# EVENTCTRL_ACQ.net
KiCad netlist of a schematic drawn in Altium Designer
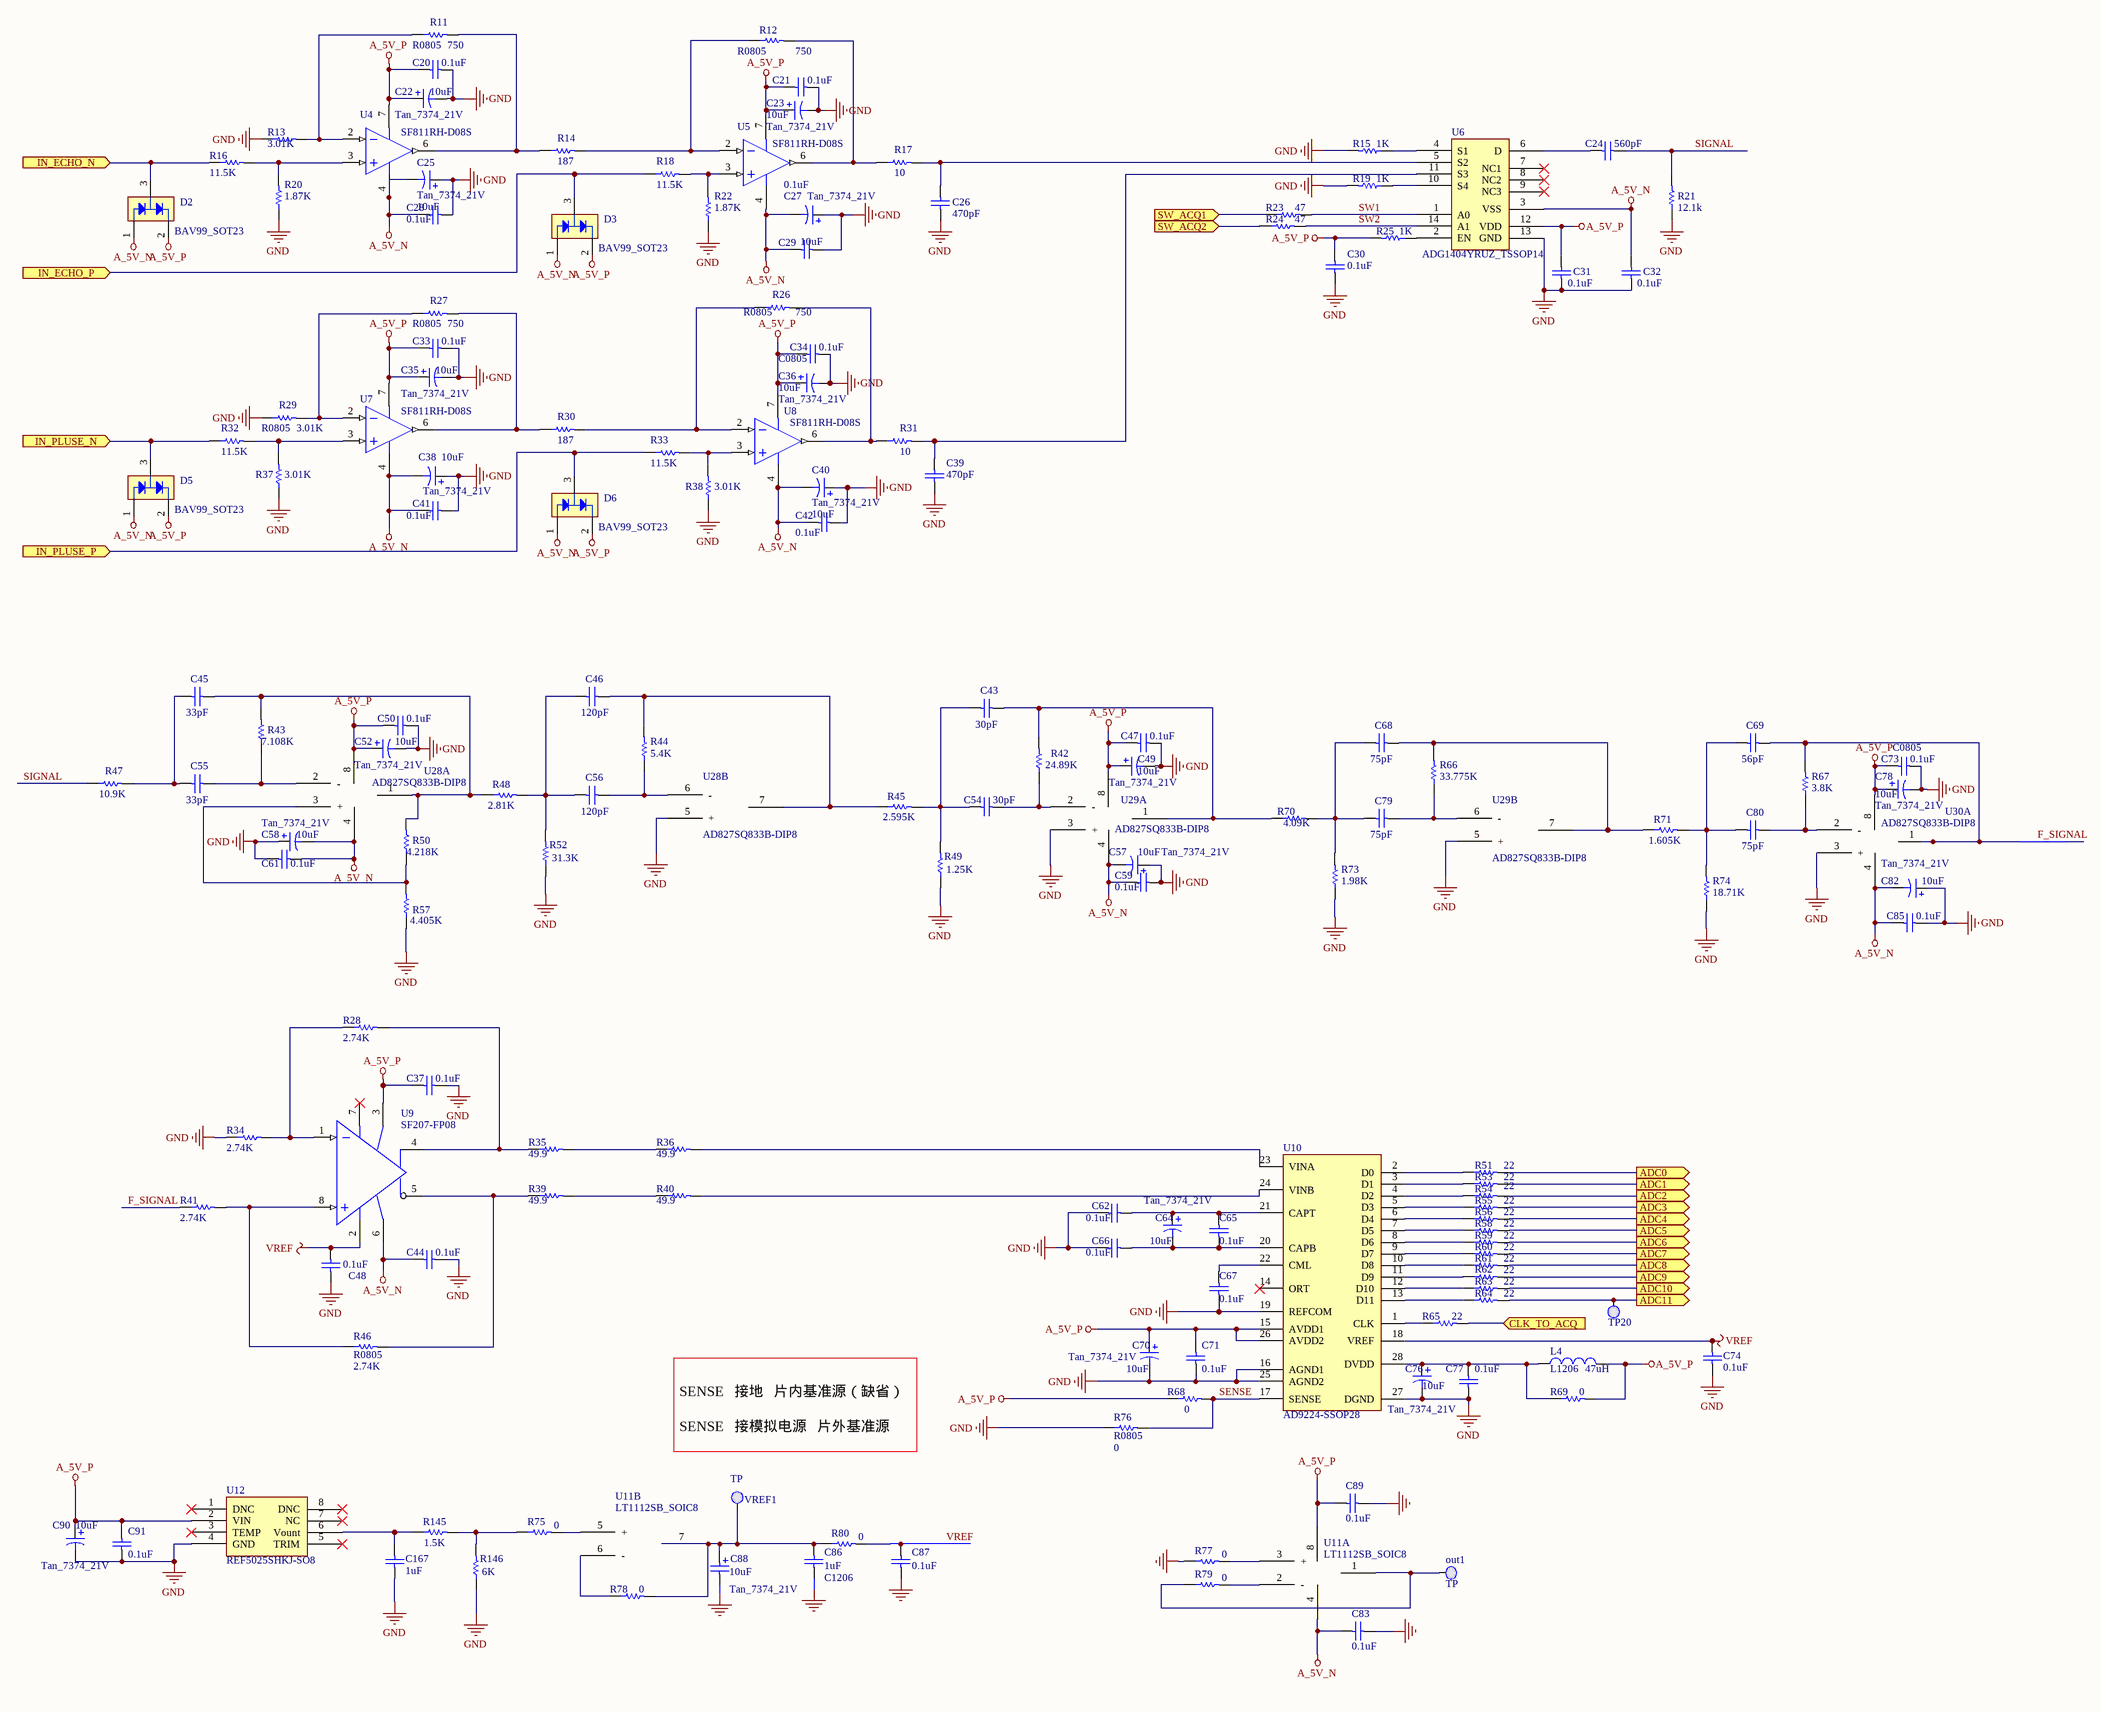
[diagram p0: EVENTCTRL_ACQ.SchDoc]

(export (version "E")
  (design (tool "Eeschema 10.0.6"))
  (components
    (comp (ref "C20")
      (value "0.1uF")
      (footprint "0805")
      (description "Capacitor")
      (fields (field (name "Comment") "C0805"))
      (libsource (lib "Miscellaneous Devices") (part "Cap"))
    )
    (comp (ref "C21")
      (value "0.1uF")
      (footprint "0805")
      (description "Capacitor")
      (fields (field (name "Comment") "C0805"))
      (libsource (lib "Miscellaneous Devices") (part "Cap"))
    )
    (comp (ref "C22")
      (value "Tan_7374_21V")
      (footprint "7343")
      (description "Polarized Capacitor (Surface Mount)")
      (fields (field (name "ALTIUM_VALUE") "10uF") (field (name "PUBLISHER") "Altium Limited"))
      (libsource (lib "Miscellaneous Devices") (part "Cap Pol3"))
    )
    (comp (ref "C23")
      (value "Tan_7374_21V")
      (footprint "7343")
      (description "Polarized Capacitor (Surface Mount)")
      (fields (field (name "ALTIUM_VALUE") "10uF") (field (name "PUBLISHER") "Altium Limited"))
      (libsource (lib "Miscellaneous Devices") (part "Cap Pol3"))
    )
    (comp (ref "C24")
      (value "560pF")
      (footprint "0805")
      (description "Capacitor")
      (fields (field (name "Comment") "C0805"))
      (libsource (lib "Miscellaneous Devices") (part "Cap"))
    )
    (comp (ref "C25")
      (value "Tan_7374_21V")
      (footprint "7343")
      (description "Polarized Capacitor (Surface Mount)")
      (fields (field (name "ALTIUM_VALUE") "10uF") (field (name "PUBLISHER") "Altium Limited"))
      (libsource (lib "Miscellaneous Devices") (part "Cap Pol3"))
    )
    (comp (ref "C26")
      (value "470pF")
      (footprint "0805")
      (description "Capacitor")
      (fields (field (name "Comment") "C0805"))
      (libsource (lib "Miscellaneous Devices") (part "Cap"))
    )
    (comp (ref "C27")
      (value "Tan_7374_21V")
      (footprint "7343")
      (description "Polarized Capacitor (Surface Mount)")
      (fields (field (name "ALTIUM_VALUE") "10uF") (field (name "PUBLISHER") "Altium Limited"))
      (libsource (lib "Miscellaneous Devices") (part "Cap Pol3"))
    )
    (comp (ref "C28")
      (value "0.1uF")
      (footprint "0805")
      (description "Capacitor")
      (fields (field (name "Comment") "C0805"))
      (libsource (lib "Miscellaneous Devices") (part "Cap"))
    )
    (comp (ref "C29")
      (value "0.1uF")
      (footprint "0805")
      (description "Capacitor")
      (fields (field (name "Comment") "C0805"))
      (libsource (lib "Miscellaneous Devices") (part "Cap"))
    )
    (comp (ref "C30")
      (value "0.1uF")
      (footprint "0805")
      (description "Capacitor")
      (fields (field (name "Comment") "C0805"))
      (libsource (lib "Miscellaneous Devices") (part "Cap"))
    )
    (comp (ref "C31")
      (value "0.1uF")
      (footprint "0805")
      (description "Capacitor")
      (fields (field (name "Comment") "C0805"))
      (libsource (lib "Miscellaneous Devices") (part "Cap"))
    )
    (comp (ref "C32")
      (value "0.1uF")
      (footprint "0805")
      (description "Capacitor")
      (fields (field (name "Comment") "C0805"))
      (libsource (lib "Miscellaneous Devices") (part "Cap"))
    )
    (comp (ref "C33")
      (value "0.1uF")
      (footprint "0805")
      (description "Capacitor")
      (fields (field (name "Comment") "C0805"))
      (libsource (lib "Miscellaneous Devices") (part "Cap"))
    )
    (comp (ref "C34")
      (value "0.1uF")
      (footprint "0805")
      (description "Capacitor")
      (fields (field (name "PACKAGEREFERENCE") "C0805") (field (name "Comment") "C0805"))
      (libsource (lib "Miscellaneous Devices") (part "Cap"))
    )
    (comp (ref "C35")
      (value "Tan_7374_21V")
      (footprint "7343")
      (description "Polarized Capacitor (Surface Mount)")
      (fields (field (name "ALTIUM_VALUE") "10uF") (field (name "PUBLISHER") "Altium Limited"))
      (libsource (lib "Miscellaneous Devices") (part "Cap Pol3"))
    )
    (comp (ref "C36")
      (value "Tan_7374_21V")
      (footprint "7343")
      (description "Polarized Capacitor (Surface Mount)")
      (fields (field (name "ALTIUM_VALUE") "10uF") (field (name "PUBLISHER") "Altium Limited"))
      (libsource (lib "Miscellaneous Devices") (part "Cap Pol3"))
    )
    (comp (ref "C37")
      (value "0.1uF")
      (footprint "0805")
      (description "Capacitor")
      (fields (field (name "Comment") "C0805"))
      (libsource (lib "Miscellaneous Devices") (part "Cap"))
    )
    (comp (ref "C38")
      (value "Tan_7374_21V")
      (footprint "7343")
      (description "Polarized Capacitor (Surface Mount)")
      (fields (field (name "ALTIUM_VALUE") "10uF") (field (name "PUBLISHER") "Altium Limited"))
      (libsource (lib "Miscellaneous Devices") (part "Cap Pol3"))
    )
    (comp (ref "C39")
      (value "470pF")
      (footprint "0805")
      (description "Capacitor")
      (fields (field (name "Comment") "C0805"))
      (libsource (lib "Miscellaneous Devices") (part "Cap"))
    )
    (comp (ref "C40")
      (value "Tan_7374_21V")
      (footprint "7343")
      (description "Polarized Capacitor (Surface Mount)")
      (fields (field (name "ALTIUM_VALUE") "10uF") (field (name "PUBLISHER") "Altium Limited"))
      (libsource (lib "Miscellaneous Devices") (part "Cap Pol3"))
    )
    (comp (ref "C41")
      (value "0.1uF")
      (footprint "0805")
      (description "Capacitor")
      (fields (field (name "Comment") "C0805"))
      (libsource (lib "Miscellaneous Devices") (part "Cap"))
    )
    (comp (ref "C42")
      (value "0.1uF")
      (footprint "0805")
      (description "Capacitor")
      (fields (field (name "Comment") "C0805"))
      (libsource (lib "Miscellaneous Devices") (part "Cap"))
    )
    (comp (ref "C43")
      (value "30pF")
      (footprint "0805")
      (description "Capacitor")
      (fields (field (name "Comment") "C0805") (field (name "PUBLISHER") "Altium Limited"))
      (libsource (lib "Miscellaneous Devices") (part "Cap"))
    )
    (comp (ref "C44")
      (value "0.1uF")
      (footprint "0805")
      (description "Capacitor")
      (fields (field (name "Comment") "C0805"))
      (libsource (lib "Miscellaneous Devices") (part "Cap"))
    )
    (comp (ref "C45")
      (value "33pF")
      (footprint "0805")
      (description "Capacitor")
      (fields (field (name "Comment") "C0805") (field (name "PUBLISHER") "Altium Limited"))
      (libsource (lib "Miscellaneous Devices") (part "Cap"))
    )
    (comp (ref "C46")
      (value "120pF")
      (footprint "0805")
      (description "Capacitor")
      (fields (field (name "Comment") "C0805") (field (name "PUBLISHER") "Altium Limited"))
      (libsource (lib "Miscellaneous Devices") (part "Cap"))
    )
    (comp (ref "C47")
      (value "0.1uF")
      (footprint "0805")
      (description "Capacitor")
      (fields (field (name "Comment") "C0805"))
      (libsource (lib "Miscellaneous Devices") (part "Cap"))
    )
    (comp (ref "C48")
      (value "0.1uF")
      (footprint "0805")
      (description "Capacitor")
      (fields (field (name "Comment") "C0805"))
      (libsource (lib "Miscellaneous Devices") (part "Cap"))
    )
    (comp (ref "C49")
      (value "Tan_7374_21V")
      (footprint "7343")
      (description "Polarized Capacitor (Surface Mount)")
      (fields (field (name "ALTIUM_VALUE") "10uF") (field (name "PUBLISHER") "Altium Limited"))
      (libsource (lib "Miscellaneous Devices") (part "Cap Pol3"))
    )
    (comp (ref "C50")
      (value "0.1uF")
      (footprint "0805")
      (description "Capacitor")
      (fields (field (name "Comment") "C0805"))
      (libsource (lib "Miscellaneous Devices") (part "Cap"))
    )
    (comp (ref "C52")
      (value "Tan_7374_21V")
      (footprint "7343")
      (description "Polarized Capacitor (Surface Mount)")
      (fields (field (name "ALTIUM_VALUE") "10uF") (field (name "PUBLISHER") "Altium Limited"))
      (libsource (lib "Miscellaneous Devices") (part "Cap Pol3"))
    )
    (comp (ref "C54")
      (value "30pF")
      (footprint "0805")
      (description "Capacitor")
      (fields (field (name "Comment") "C0805") (field (name "PUBLISHER") "Altium Limited"))
      (libsource (lib "Miscellaneous Devices") (part "Cap"))
    )
    (comp (ref "C55")
      (value "33pF")
      (footprint "0805")
      (description "Capacitor")
      (fields (field (name "Comment") "C0805") (field (name "PUBLISHER") "Altium Limited"))
      (libsource (lib "Miscellaneous Devices") (part "Cap"))
    )
    (comp (ref "C56")
      (value "120pF")
      (footprint "0805")
      (description "Capacitor")
      (fields (field (name "Comment") "C0805") (field (name "PUBLISHER") "Altium Limited"))
      (libsource (lib "Miscellaneous Devices") (part "Cap"))
    )
    (comp (ref "C57")
      (value "Tan_7374_21V")
      (footprint "7343")
      (description "Polarized Capacitor (Surface Mount)")
      (fields (field (name "ALTIUM_VALUE") "10uF") (field (name "PUBLISHER") "Altium Limited"))
      (libsource (lib "Miscellaneous Devices") (part "Cap Pol3"))
    )
    (comp (ref "C58")
      (value "Tan_7374_21V")
      (footprint "7343")
      (description "Polarized Capacitor (Surface Mount)")
      (fields (field (name "ALTIUM_VALUE") "10uF") (field (name "PUBLISHER") "Altium Limited"))
      (libsource (lib "Miscellaneous Devices") (part "Cap Pol3"))
    )
    (comp (ref "C59")
      (value "0.1uF")
      (footprint "0805")
      (description "Capacitor")
      (fields (field (name "Comment") "C0805"))
      (libsource (lib "Miscellaneous Devices") (part "Cap"))
    )
    (comp (ref "C61")
      (value "0.1uF")
      (footprint "0805")
      (description "Capacitor")
      (fields (field (name "Comment") "C0805"))
      (libsource (lib "Miscellaneous Devices") (part "Cap"))
    )
    (comp (ref "C62")
      (value "0.1uF")
      (footprint "0805")
      (description "Capacitor")
      (fields (field (name "Comment") "C0805"))
      (libsource (lib "Miscellaneous Devices") (part "Cap"))
    )
    (comp (ref "C64")
      (value "Tan_7374_21V")
      (footprint "7343")
      (description "Polarized Capacitor (Radial)")
      (fields (field (name "ALTIUM_VALUE") "10uF"))
      (libsource (lib "Miscellaneous Devices") (part "Cap Pol1"))
    )
    (comp (ref "C65")
      (value "0.1uF")
      (footprint "0805")
      (description "Capacitor")
      (fields (field (name "Comment") "C0805"))
      (libsource (lib "Miscellaneous Devices") (part "Cap"))
    )
    (comp (ref "C66")
      (value "0.1uF")
      (footprint "0805")
      (description "Capacitor")
      (fields (field (name "Comment") "C0805"))
      (libsource (lib "Miscellaneous Devices") (part "Cap"))
    )
    (comp (ref "C67")
      (value "0.1uF")
      (footprint "0805")
      (description "Capacitor")
      (fields (field (name "Comment") "C0805"))
      (libsource (lib "Miscellaneous Devices") (part "Cap"))
    )
    (comp (ref "C68")
      (value "75pF")
      (footprint "0805")
      (description "Capacitor")
      (fields (field (name "Comment") "C0805") (field (name "PUBLISHER") "Altium Limited"))
      (libsource (lib "Miscellaneous Devices") (part "Cap"))
    )
    (comp (ref "C69")
      (value "56pF")
      (footprint "0805")
      (description "Capacitor")
      (fields (field (name "Comment") "C0805") (field (name "PUBLISHER") "Altium Limited"))
      (libsource (lib "Miscellaneous Devices") (part "Cap"))
    )
    (comp (ref "C70")
      (value "Tan_7374_21V")
      (footprint "7343")
      (description "Polarized Capacitor (Radial)")
      (fields (field (name "ALTIUM_VALUE") "10uF"))
      (libsource (lib "Miscellaneous Devices") (part "Cap Pol1"))
    )
    (comp (ref "C71")
      (value "0.1uF")
      (footprint "0805")
      (description "Capacitor")
      (fields (field (name "Comment") "C0805"))
      (libsource (lib "Miscellaneous Devices") (part "Cap"))
    )
    (comp (ref "C73")
      (value "0.1uF")
      (footprint "0805")
      (description "Capacitor")
      (fields (field (name "PACKAGEREFERENCE") "C0805") (field (name "Comment") "C0805"))
      (libsource (lib "Miscellaneous Devices") (part "Cap"))
    )
    (comp (ref "C74")
      (value "0.1uF")
      (footprint "0805")
      (description "Capacitor")
      (fields (field (name "Comment") "C0805"))
      (libsource (lib "Miscellaneous Devices") (part "Cap"))
    )
    (comp (ref "C76")
      (value "Tan_7374_21V")
      (footprint "7343")
      (description "Polarized Capacitor (Radial)")
      (fields (field (name "ALTIUM_VALUE") "10uF"))
      (libsource (lib "Miscellaneous Devices") (part "Cap Pol1"))
    )
    (comp (ref "C77")
      (value "0.1uF")
      (footprint "0805")
      (description "Capacitor")
      (fields (field (name "Comment") "C0805"))
      (libsource (lib "Miscellaneous Devices") (part "Cap"))
    )
    (comp (ref "C78")
      (value "Tan_7374_21V")
      (footprint "7343")
      (description "Polarized Capacitor (Surface Mount)")
      (fields (field (name "ALTIUM_VALUE") "10uF") (field (name "PUBLISHER") "Altium Limited"))
      (libsource (lib "Miscellaneous Devices") (part "Cap Pol3"))
    )
    (comp (ref "C79")
      (value "75pF")
      (footprint "0805")
      (description "Capacitor")
      (fields (field (name "Comment") "C0805") (field (name "PUBLISHER") "Altium Limited"))
      (libsource (lib "Miscellaneous Devices") (part "Cap"))
    )
    (comp (ref "C80")
      (value "75pF")
      (footprint "0805")
      (description "Capacitor")
      (fields (field (name "Comment") "C0805") (field (name "PUBLISHER") "Altium Limited"))
      (libsource (lib "Miscellaneous Devices") (part "Cap"))
    )
    (comp (ref "C82")
      (value "Tan_7374_21V")
      (footprint "7343")
      (description "Polarized Capacitor (Surface Mount)")
      (fields (field (name "ALTIUM_VALUE") "10uF") (field (name "PUBLISHER") "Altium Limited"))
      (libsource (lib "Miscellaneous Devices") (part "Cap Pol3"))
    )
    (comp (ref "C83")
      (value "0.1uF")
      (footprint "0805")
      (description "Capacitor")
      (fields (field (name "PART NUMBER") "Y20021820") (field (name "Comment") "C0805"))
      (libsource (lib "电容") (part "Y20021820"))
    )
    (comp (ref "C85")
      (value "0.1uF")
      (footprint "0805")
      (description "Capacitor")
      (fields (field (name "Comment") "C0805"))
      (libsource (lib "Miscellaneous Devices") (part "Cap"))
    )
    (comp (ref "C86")
      (value "C1206")
      (footprint "1206")
      (description "Capacitor")
      (fields (field (name "ALTIUM_VALUE") "1uF") (field (name "PART NUMBER") "Y20021820"))
      (libsource (lib "电容") (part "Y20021820"))
    )
    (comp (ref "C87")
      (value "0.1uF")
      (footprint "0805")
      (description "Capacitor")
      (fields (field (name "PART NUMBER") "Y20021820") (field (name "Comment") "C0805"))
      (libsource (lib "电容") (part "Y20021820"))
    )
    (comp (ref "C88")
      (value "Tan_7374_21V")
      (footprint "7343")
      (description "Polarized Capacitor")
      (fields (field (name "ALTIUM_VALUE") "10uF") (field (name "PART NUMBER") "Y20024818"))
      (libsource (lib "电容") (part "Y20024818"))
    )
    (comp (ref "C89")
      (value "0.1uF")
      (footprint "0805")
      (description "Capacitor")
      (fields (field (name "PART NUMBER") "Y20021820") (field (name "Comment") "C0805"))
      (libsource (lib "电容") (part "Y20021820"))
    )
    (comp (ref "C90")
      (value "Tan_7374_21V")
      (footprint "7343")
      (description "Polarized Capacitor (Surface Mount)")
      (fields (field (name "ALTIUM_VALUE") "10uF") (field (name "PUBLISHER") "Altium Limited"))
      (libsource (lib "Miscellaneous Devices") (part "Cap Pol3"))
    )
    (comp (ref "C91")
      (value "0.1uF")
      (footprint "0805")
      (description "Capacitor")
      (fields (field (name "Comment") "C0805"))
      (libsource (lib "Miscellaneous Devices") (part "Cap"))
    )
    (comp (ref "C167")
      (value "1uF")
      (footprint "1206")
      (description "Capacitor")
      (fields (field (name "Comment") "C1206"))
      (libsource (lib "Miscellaneous Devices") (part "Cap"))
    )
    (comp (ref "D2") (value "BAV99_SOT23") (footprint "SOT23-3N") (libsource (lib "*") (part "BAV99LT1")))
    (comp (ref "D3") (value "BAV99_SOT23") (footprint "SOT23-3N") (libsource (lib "*") (part "BAV99LT1")))
    (comp (ref "D5") (value "BAV99_SOT23") (footprint "SOT23-3N") (libsource (lib "*") (part "BAV99LT1")))
    (comp (ref "D6") (value "BAV99_SOT23") (footprint "SOT23-3N") (libsource (lib "*") (part "BAV99LT1")))
    (comp (ref "L4")
      (value "L1206")
      (footprint "1206")
      (description "Inductor")
      (fields (field (name "ALTIUM_VALUE") "47uH"))
      (libsource (lib "Miscellaneous Devices") (part "Inductor"))
    )
    (comp (ref "out1") (value "TP") (footprint "TPA") (libsource (lib "Test") (part "TP")))
    (comp (ref "R11")
      (value "750")
      (footprint "R0805")
      (description "Resistor")
      (fields (field (name "PACKAGEREFERENCE") "R0805") (field (name "Comment") "R0805"))
      (libsource (lib "Miscellaneous Devices") (part "Res1"))
    )
    (comp (ref "R12")
      (value "R0805")
      (footprint "R0805")
      (description "Resistor")
      (fields (field (name "ALTIUM_VALUE") "750") (field (name "PUBLISHER") "Altium Limited"))
      (libsource (lib "Miscellaneous Devices") (part "Res1"))
    )
    (comp (ref "R13")
      (value "3.01K")
      (footprint "R0805")
      (description "Resistor")
      (fields (field (name "Comment") "R0805"))
      (libsource (lib "Miscellaneous Devices") (part "Res1"))
    )
    (comp (ref "R14")
      (value "187")
      (footprint "R0805")
      (description "Resistor")
      (fields (field (name "Comment") "R0805") (field (name "PUBLISHER") "Altium Limited"))
      (libsource (lib "Miscellaneous Devices") (part "Res1"))
    )
    (comp (ref "R15")
      (value "1K")
      (footprint "R0805")
      (description "Resistor")
      (fields (field (name "Comment") "R0805"))
      (libsource (lib "Miscellaneous Devices") (part "Res1"))
    )
    (comp (ref "R16")
      (value "11.5K")
      (footprint "R0805")
      (description "Resistor")
      (fields (field (name "Comment") "R0805"))
      (libsource (lib "Miscellaneous Devices") (part "Res1"))
    )
    (comp (ref "R17")
      (value "10")
      (footprint "R0805")
      (description "Resistor")
      (fields (field (name "Comment") "R0805"))
      (libsource (lib "Miscellaneous Devices") (part "Res1"))
    )
    (comp (ref "R18")
      (value "11.5K")
      (footprint "R0805")
      (description "Resistor")
      (fields (field (name "Comment") "R0805"))
      (libsource (lib "Miscellaneous Devices") (part "Res1"))
    )
    (comp (ref "R19")
      (value "1K")
      (footprint "R0805")
      (description "Resistor")
      (fields (field (name "Comment") "R0805"))
      (libsource (lib "Miscellaneous Devices") (part "Res1"))
    )
    (comp (ref "R20")
      (value "1.87K")
      (footprint "R0805")
      (description "Resistor")
      (fields (field (name "Comment") "R0805"))
      (libsource (lib "Miscellaneous Devices") (part "Res1"))
    )
    (comp (ref "R21")
      (value "12.1k")
      (footprint "R0805")
      (description "Resistor")
      (fields (field (name "Comment") "R0805"))
      (libsource (lib "Miscellaneous Devices") (part "Res1"))
    )
    (comp (ref "R22")
      (value "1.87K")
      (footprint "R0805")
      (description "Resistor")
      (fields (field (name "Comment") "R0805"))
      (libsource (lib "Miscellaneous Devices") (part "Res1"))
    )
    (comp (ref "R23")
      (value "47")
      (footprint "R0805")
      (description "Resistor")
      (fields (field (name "Comment") "R0805"))
      (libsource (lib "Miscellaneous Devices") (part "Res1"))
    )
    (comp (ref "R24")
      (value "47")
      (footprint "R0805")
      (description "Resistor")
      (fields (field (name "Comment") "R0805"))
      (libsource (lib "Miscellaneous Devices") (part "Res1"))
    )
    (comp (ref "R25")
      (value "1K")
      (footprint "R0805")
      (description "Resistor")
      (fields (field (name "Comment") "R0805"))
      (libsource (lib "Miscellaneous Devices") (part "Res1"))
    )
    (comp (ref "R26")
      (value "750")
      (footprint "R0805")
      (description "Resistor")
      (fields (field (name "PACKAGEREFERENCE") "R0805") (field (name "Comment") "R0805"))
      (libsource (lib "Miscellaneous Devices") (part "Res1"))
    )
    (comp (ref "R27")
      (value "750")
      (footprint "R0805")
      (description "Resistor")
      (fields (field (name "PACKAGEREFERENCE") "R0805") (field (name "Comment") "R0805"))
      (libsource (lib "Miscellaneous Devices") (part "Res1"))
    )
    (comp (ref "R28")
      (value "2.74K")
      (footprint "R0805")
      (description "Resistor")
      (fields (field (name "Comment") "R0805"))
      (libsource (lib "Miscellaneous Devices") (part "Res1"))
    )
    (comp (ref "R29")
      (value "3.01K")
      (footprint "R0805")
      (description "Resistor")
      (fields (field (name "PACKAGEREFERENCE") "R0805") (field (name "Comment") "R0805"))
      (libsource (lib "Miscellaneous Devices") (part "Res1"))
    )
    (comp (ref "R30")
      (value "187")
      (footprint "R0805")
      (description "Resistor")
      (fields (field (name "Comment") "R0805"))
      (libsource (lib "Miscellaneous Devices") (part "Res1"))
    )
    (comp (ref "R31")
      (value "10")
      (footprint "R0805")
      (description "Resistor")
      (fields (field (name "Comment") "R0805"))
      (libsource (lib "Miscellaneous Devices") (part "Res1"))
    )
    (comp (ref "R32")
      (value "11.5K")
      (footprint "R0805")
      (description "Resistor")
      (fields (field (name "Comment") "R0805"))
      (libsource (lib "Miscellaneous Devices") (part "Res1"))
    )
    (comp (ref "R33")
      (value "11.5K")
      (footprint "R0805")
      (description "Resistor")
      (fields (field (name "Comment") "R0805"))
      (libsource (lib "Miscellaneous Devices") (part "Res1"))
    )
    (comp (ref "R34")
      (value "2.74K")
      (footprint "R0805")
      (description "Resistor")
      (fields (field (name "Comment") "R0805"))
      (libsource (lib "Miscellaneous Devices") (part "Res1"))
    )
    (comp (ref "R35")
      (value "49.9")
      (footprint "R0805")
      (description "Resistor")
      (fields (field (name "Comment") "R0805"))
      (libsource (lib "Miscellaneous Devices") (part "Res1"))
    )
    (comp (ref "R36")
      (value "49.9")
      (footprint "R0805")
      (description "Resistor")
      (fields (field (name "Comment") "R0805"))
      (libsource (lib "Miscellaneous Devices") (part "Res1"))
    )
    (comp (ref "R37")
      (value "3.01K")
      (footprint "R0805")
      (description "Resistor")
      (fields (field (name "Comment") "R0805"))
      (libsource (lib "Miscellaneous Devices") (part "Res1"))
    )
    (comp (ref "R38")
      (value "3.01K")
      (footprint "R0805")
      (description "Resistor")
      (fields (field (name "Comment") "R0805"))
      (libsource (lib "Miscellaneous Devices") (part "Res1"))
    )
    (comp (ref "R39")
      (value "49.9")
      (footprint "R0805")
      (description "Resistor")
      (fields (field (name "Comment") "R0805"))
      (libsource (lib "Miscellaneous Devices") (part "Res1"))
    )
    (comp (ref "R40")
      (value "49.9")
      (footprint "R0805")
      (description "Resistor")
      (fields (field (name "Comment") "R0805"))
      (libsource (lib "Miscellaneous Devices") (part "Res1"))
    )
    (comp (ref "R41")
      (value "2.74K")
      (footprint "R0805")
      (description "Resistor")
      (fields (field (name "Comment") "R0805"))
      (libsource (lib "Miscellaneous Devices") (part "Res1"))
    )
    (comp (ref "R42")
      (value "24.89K")
      (footprint "R0805")
      (description "Resistor")
      (fields (field (name "Comment") "R0805") (field (name "PUBLISHER") "Altium Limited"))
      (libsource (lib "Miscellaneous Devices") (part "Res1"))
    )
    (comp (ref "R43")
      (value "7.108K")
      (footprint "R0805")
      (description "Resistor")
      (fields (field (name "Comment") "R0805") (field (name "PUBLISHER") "Altium Limited"))
      (libsource (lib "Miscellaneous Devices") (part "Res1"))
    )
    (comp (ref "R44")
      (value "5.4K")
      (footprint "R0805")
      (description "Resistor")
      (fields (field (name "Comment") "R0805") (field (name "PUBLISHER") "Altium Limited"))
      (libsource (lib "Miscellaneous Devices") (part "Res1"))
    )
    (comp (ref "R45")
      (value "2.595K")
      (footprint "R0805")
      (description "Resistor")
      (fields (field (name "Comment") "R0805") (field (name "PUBLISHER") "Altium Limited"))
      (libsource (lib "Miscellaneous Devices") (part "Res1"))
    )
    (comp (ref "R46")
      (value "R0805")
      (footprint "R0805")
      (description "Resistor")
      (fields (field (name "ALTIUM_VALUE") "2.74K"))
      (libsource (lib "Miscellaneous Devices") (part "Res1"))
    )
    (comp (ref "R47")
      (value "10.9K")
      (footprint "R0805")
      (description "Resistor")
      (fields (field (name "Comment") "R0805") (field (name "PUBLISHER") "Altium Limited"))
      (libsource (lib "Miscellaneous Devices") (part "Res1"))
    )
    (comp (ref "R48")
      (value "2.81K")
      (footprint "R0805")
      (description "Resistor")
      (fields (field (name "Comment") "R0805") (field (name "PUBLISHER") "Altium Limited"))
      (libsource (lib "Miscellaneous Devices") (part "Res1"))
    )
    (comp (ref "R49")
      (value "1.25K")
      (footprint "R0805")
      (description "Resistor")
      (fields (field (name "Comment") "R0805") (field (name "PUBLISHER") "Altium Limited"))
      (libsource (lib "Miscellaneous Devices") (part "Res1"))
    )
    (comp (ref "R50")
      (value "4.218K")
      (footprint "R0805")
      (description "Resistor")
      (fields (field (name "Comment") "R0805") (field (name "PUBLISHER") "Altium Limited"))
      (libsource (lib "Miscellaneous Devices") (part "Res1"))
    )
    (comp (ref "R51")
      (value "22")
      (footprint "R0805")
      (description "Resistor")
      (fields (field (name "Comment") "R0805") (field (name "PUBLISHER") "Altium Limited"))
      (libsource (lib "Miscellaneous Devices") (part "Res1"))
    )
    (comp (ref "R52")
      (value "31.3K")
      (footprint "R0805")
      (description "Resistor")
      (fields (field (name "Comment") "R0805") (field (name "PUBLISHER") "Altium Limited"))
      (libsource (lib "Miscellaneous Devices") (part "Res1"))
    )
    (comp (ref "R53")
      (value "22")
      (footprint "R0805")
      (description "Resistor")
      (fields (field (name "Comment") "R0805") (field (name "PUBLISHER") "Altium Limited"))
      (libsource (lib "Miscellaneous Devices") (part "Res1"))
    )
    (comp (ref "R54")
      (value "22")
      (footprint "R0805")
      (description "Resistor")
      (fields (field (name "Comment") "R0805") (field (name "PUBLISHER") "Altium Limited"))
      (libsource (lib "Miscellaneous Devices") (part "Res1"))
    )
    (comp (ref "R55")
      (value "22")
      (footprint "R0805")
      (description "Resistor")
      (fields (field (name "Comment") "R0805") (field (name "PUBLISHER") "Altium Limited"))
      (libsource (lib "Miscellaneous Devices") (part "Res1"))
    )
    (comp (ref "R56")
      (value "22")
      (footprint "R0805")
      (description "Resistor")
      (fields (field (name "Comment") "R0805") (field (name "PUBLISHER") "Altium Limited"))
      (libsource (lib "Miscellaneous Devices") (part "Res1"))
    )
    (comp (ref "R57")
      (value "4.405K")
      (footprint "R0805")
      (description "Resistor")
      (fields (field (name "Comment") "R0805") (field (name "PUBLISHER") "Altium Limited"))
      (libsource (lib "Miscellaneous Devices") (part "Res1"))
    )
    (comp (ref "R58")
      (value "22")
      (footprint "R0805")
      (description "Resistor")
      (fields (field (name "Comment") "R0805") (field (name "PUBLISHER") "Altium Limited"))
      (libsource (lib "Miscellaneous Devices") (part "Res1"))
    )
    (comp (ref "R59")
      (value "22")
      (footprint "R0805")
      (description "Resistor")
      (fields (field (name "Comment") "R0805") (field (name "PUBLISHER") "Altium Limited"))
      (libsource (lib "Miscellaneous Devices") (part "Res1"))
    )
    (comp (ref "R60")
      (value "22")
      (footprint "R0805")
      (description "Resistor")
      (fields (field (name "Comment") "R0805") (field (name "PUBLISHER") "Altium Limited"))
      (libsource (lib "Miscellaneous Devices") (part "Res1"))
    )
    (comp (ref "R61")
      (value "22")
      (footprint "R0805")
      (description "Resistor")
      (fields (field (name "Comment") "R0805") (field (name "PUBLISHER") "Altium Limited"))
      (libsource (lib "Miscellaneous Devices") (part "Res1"))
    )
    (comp (ref "R62")
      (value "22")
      (footprint "R0805")
      (description "Resistor")
      (fields (field (name "Comment") "R0805") (field (name "PUBLISHER") "Altium Limited"))
      (libsource (lib "Miscellaneous Devices") (part "Res1"))
    )
    (comp (ref "R63")
      (value "22")
      (footprint "R0805")
      (description "Resistor")
      (fields (field (name "Comment") "R0805") (field (name "PUBLISHER") "Altium Limited"))
      (libsource (lib "Miscellaneous Devices") (part "Res1"))
    )
    (comp (ref "R64")
      (value "22")
      (footprint "R0805")
      (description "Resistor")
      (fields (field (name "Comment") "R0805") (field (name "PUBLISHER") "Altium Limited"))
      (libsource (lib "Miscellaneous Devices") (part "Res1"))
    )
    (comp (ref "R65")
      (value "22")
      (footprint "R0805")
      (description "Resistor")
      (fields (field (name "Comment") "R0805"))
      (libsource (lib "Miscellaneous Devices") (part "Res1"))
    )
    (comp (ref "R66")
      (value "33.775K")
      (footprint "R0805")
      (description "Resistor")
      (fields (field (name "Comment") "R0805") (field (name "PUBLISHER") "Altium Limited"))
      (libsource (lib "Miscellaneous Devices") (part "Res1"))
    )
    (comp (ref "R67")
      (value "3.8K")
      (footprint "R0805")
      (description "Resistor")
      (fields (field (name "Comment") "R0805") (field (name "PUBLISHER") "Altium Limited"))
      (libsource (lib "Miscellaneous Devices") (part "Res1"))
    )
    (comp (ref "R68")
      (value "0")
      (footprint "R0805")
      (description "Resistor")
      (fields (field (name "Comment") "R0805"))
      (libsource (lib "Miscellaneous Devices") (part "Res1"))
    )
    (comp (ref "R69")
      (value "0")
      (footprint "R0805")
      (description "Resistor")
      (fields (field (name "Comment") "R0805"))
      (libsource (lib "Miscellaneous Devices") (part "Res1"))
    )
    (comp (ref "R70")
      (value "4.09K")
      (footprint "R0805")
      (description "Resistor")
      (fields (field (name "Comment") "R0805") (field (name "PUBLISHER") "Altium Limited"))
      (libsource (lib "Miscellaneous Devices") (part "Res1"))
    )
    (comp (ref "R71")
      (value "1.605K")
      (footprint "R0805")
      (description "Resistor")
      (fields (field (name "Comment") "R0805") (field (name "PUBLISHER") "Altium Limited"))
      (libsource (lib "Miscellaneous Devices") (part "Res1"))
    )
    (comp (ref "R73")
      (value "1.98K")
      (footprint "R0805")
      (description "Resistor")
      (fields (field (name "Comment") "R0805") (field (name "PUBLISHER") "Altium Limited"))
      (libsource (lib "Miscellaneous Devices") (part "Res1"))
    )
    (comp (ref "R74")
      (value "18.71K")
      (footprint "R0805")
      (description "Resistor")
      (fields (field (name "Comment") "R0805") (field (name "PUBLISHER") "Altium Limited"))
      (libsource (lib "Miscellaneous Devices") (part "Res1"))
    )
    (comp (ref "R75")
      (value "0")
      (footprint "R0805")
      (description "Resistor")
      (fields (field (name "Comment") "R0805") (field (name "PUBLISHER") "Altium Limited"))
      (libsource (lib "Miscellaneous Devices") (part "Res1"))
    )
    (comp (ref "R76")
      (value "0")
      (footprint "R0805")
      (description "Resistor")
      (fields (field (name "PACKAGEREFERENCE") "R0805") (field (name "Comment") "R0805"))
      (libsource (lib "Miscellaneous Devices") (part "Res1"))
    )
    (comp (ref "R77")
      (value "0")
      (footprint "R0805")
      (description "Resistor")
      (fields (field (name "Comment") "R0805") (field (name "PUBLISHER") "Altium Limited"))
      (libsource (lib "Miscellaneous Devices") (part "Res1"))
    )
    (comp (ref "R78")
      (value "0")
      (footprint "R0805")
      (description "Resistor")
      (fields (field (name "Comment") "R0805") (field (name "PUBLISHER") "Altium Limited"))
      (libsource (lib "Miscellaneous Devices") (part "Res1"))
    )
    (comp (ref "R79")
      (value "0")
      (footprint "R0805")
      (description "Resistor")
      (fields (field (name "Comment") "R0805") (field (name "PUBLISHER") "Altium Limited"))
      (libsource (lib "Miscellaneous Devices") (part "Res1"))
    )
    (comp (ref "R80")
      (value "0")
      (footprint "R0805")
      (description "Resistor")
      (fields (field (name "Comment") "R0805") (field (name "PUBLISHER") "Altium Limited"))
      (libsource (lib "Miscellaneous Devices") (part "Res1"))
    )
    (comp (ref "R145")
      (value "1.5K")
      (footprint "R0805")
      (description "Resistor")
      (fields (field (name "Comment") "R0805") (field (name "PUBLISHER") "Altium Limited"))
      (libsource (lib "Miscellaneous Devices") (part "Res1"))
    )
    (comp (ref "R146")
      (value "6K")
      (footprint "R0805")
      (description "Resistor")
      (fields (field (name "Comment") "R0805") (field (name "PUBLISHER") "Altium Limited"))
      (libsource (lib "Miscellaneous Devices") (part "Res1"))
    )
    (comp (ref "TP20") (value "TP") (footprint "TPA") (libsource (lib "*") (part "TP")))
    (comp (ref "U4") (value "SF811RH-D08S") (footprint "DIP8") (libsource (lib "srj") (part "AD811")))
    (comp (ref "U5") (value "SF811RH-D08S") (footprint "DIP8") (libsource (lib "srj") (part "AD811")))
    (comp (ref "U6")
      (value "ADG1404YRUZ_TSSOP14")
      (footprint "TSSOP14")
      (libsource (lib "srj") (part "ADG1404"))
    )
    (comp (ref "U7") (value "SF811RH-D08S") (footprint "DIP8") (libsource (lib "srj") (part "AD811")))
    (comp (ref "U8") (value "SF811RH-D08S") (footprint "DIP8") (libsource (lib "srj") (part "AD811")))
    (comp (ref "U9") (value "SF207-FP08") (footprint "SO-8") (libsource (lib "srj") (part "SF207")))
    (comp (ref "U10") (value "AD9224-SSOP28") (footprint "TSSOP28") (libsource (lib "srj") (part "AD9224")))
    (comp (ref "U11") (value "LT1112SB_SOIC8") (footprint "SO-8") (libsource (lib "srj") (part "LT1112SB")))
    (comp (ref "U12")
      (value "REF5025SHKJ-SO8")
      (footprint "SO8-HKJ")
      (libsource (lib "REF_5025HT") (part "Component_1"))
    )
    (comp (ref "U28") (value "AD827SQ833B-DIP8") (footprint "DIP8") (libsource (lib "srj") (part "AD827")))
    (comp (ref "U29") (value "AD827SQ833B-DIP8") (footprint "DIP8") (libsource (lib "srj") (part "AD827")))
    (comp (ref "U30") (value "AD827SQ833B-DIP8") (footprint "DIP8") (libsource (lib "srj") (part "AD827")))
    (comp (ref "VREF1") (value "TP") (footprint "TPA") (libsource (lib "") (part "TP_1")))
  )
  (nets
    (net (code "1") (name "/ADC0") (class "Default")
      (node (ref "R51") (pin "2") (pinfunction "2_2") (pintype "passive"))
    )
    (net (code "2") (name "/ADC1") (class "Default")
      (node (ref "R53") (pin "2") (pinfunction "2_2") (pintype "passive"))
    )
    (net (code "3") (name "/ADC2") (class "Default")
      (node (ref "R54") (pin "2") (pinfunction "2_2") (pintype "passive"))
    )
    (net (code "4") (name "/ADC3") (class "Default")
      (node (ref "R55") (pin "2") (pinfunction "2_2") (pintype "passive"))
    )
    (net (code "5") (name "/ADC4") (class "Default")
      (node (ref "R56") (pin "2") (pinfunction "2_2") (pintype "passive"))
    )
    (net (code "6") (name "/ADC5") (class "Default")
      (node (ref "R58") (pin "2") (pinfunction "2_2") (pintype "passive"))
    )
    (net (code "7") (name "/ADC6") (class "Default")
      (node (ref "R59") (pin "2") (pinfunction "2_2") (pintype "passive"))
    )
    (net (code "8") (name "/ADC7") (class "Default")
      (node (ref "R60") (pin "2") (pinfunction "2_2") (pintype "passive"))
    )
    (net (code "9") (name "/ADC8") (class "Default")
      (node (ref "R61") (pin "2") (pinfunction "2_2") (pintype "passive"))
    )
    (net (code "10") (name "/ADC9") (class "Default")
      (node (ref "R62") (pin "2") (pinfunction "2_2") (pintype "passive"))
    )
    (net (code "11") (name "/ADC10") (class "Default")
      (node (ref "R63") (pin "2") (pinfunction "2_2") (pintype "passive"))
    )
    (net (code "12") (name "/ADC11") (class "Default")
      (node (ref "R64") (pin "2") (pinfunction "2_2") (pintype "passive"))
      (node (ref "TP20") (pin "1") (pinfunction "TP_1") (pintype "passive"))
    )
    (net (code "13") (name "/CLK_TO_ACQ") (class "Default")
      (node (ref "R65") (pin "2") (pinfunction "2_2") (pintype "passive"))
    )
    (net (code "14") (name "/F_SIGNAL") (class "Default")
      (node (ref "C69") (pin "2") (pinfunction "2_2") (pintype "passive"))
      (node (ref "R41") (pin "1") (pinfunction "1_1") (pintype "passive"))
      (node (ref "R67") (pin "2") (pinfunction "2_2") (pintype "passive"))
      (node (ref "U30") (pin "1") (pinfunction "OUTA_1") (pintype "passive"))
    )
    (net (code "15") (name "/IN_ECHO_N") (class "Default")
      (node (ref "D2") (pin "3") (pinfunction "3_3") (pintype "passive"))
      (node (ref "R16") (pin "1") (pinfunction "1_1") (pintype "passive"))
    )
    (net (code "16") (name "/IN_ECHO_P") (class "Default")
      (node (ref "D3") (pin "3") (pinfunction "3_3") (pintype "passive"))
      (node (ref "R18") (pin "1") (pinfunction "1_1") (pintype "passive"))
    )
    (net (code "17") (name "/IN_PLUSE_N") (class "Default")
      (node (ref "D5") (pin "3") (pinfunction "3_3") (pintype "passive"))
      (node (ref "R32") (pin "1") (pinfunction "1_1") (pintype "passive"))
    )
    (net (code "18") (name "/IN_PLUSE_P") (class "Default")
      (node (ref "D6") (pin "3") (pinfunction "3_3") (pintype "passive"))
      (node (ref "R33") (pin "1") (pinfunction "1_1") (pintype "passive"))
    )
    (net (code "19") (name "/SENSE") (class "Default")
      (node (ref "R68") (pin "2") (pinfunction "2_2") (pintype "passive"))
      (node (ref "R76") (pin "2") (pinfunction "2_2") (pintype "passive"))
      (node (ref "U10") (pin "17") (pinfunction "SENSE_17") (pintype "passive"))
    )
    (net (code "20") (name "/SIGNAL") (class "Default")
      (node (ref "C24") (pin "2") (pinfunction "2_2") (pintype "passive"))
      (node (ref "R21") (pin "2") (pinfunction "2_2") (pintype "passive"))
      (node (ref "R47") (pin "1") (pinfunction "1_1") (pintype "passive"))
    )
    (net (code "21") (name "/SW1") (class "Default")
      (node (ref "R23") (pin "2") (pinfunction "2_2") (pintype "passive"))
      (node (ref "U6") (pin "1") (pinfunction "A0_1") (pintype "passive"))
    )
    (net (code "22") (name "/SW2") (class "Default")
      (node (ref "R24") (pin "2") (pinfunction "2_2") (pintype "passive"))
      (node (ref "U6") (pin "14") (pinfunction "A1_14") (pintype "passive"))
    )
    (net (code "23") (name "/SW_ACQ1") (class "Default")
      (node (ref "R23") (pin "1") (pinfunction "1_1") (pintype "passive"))
    )
    (net (code "24") (name "/SW_ACQ2") (class "Default")
      (node (ref "R24") (pin "1") (pinfunction "1_1") (pintype "passive"))
    )
    (net (code "25") (name "A_5V_N") (class "Default")
      (node (ref "C25") (pin "2") (pinfunction "2_2") (pintype "passive"))
      (node (ref "C27") (pin "2") (pinfunction "2_2") (pintype "passive"))
      (node (ref "C28") (pin "1") (pinfunction "1_1") (pintype "passive"))
      (node (ref "C29") (pin "1") (pinfunction "1_1") (pintype "passive"))
      (node (ref "C32") (pin "1") (pinfunction "1_1") (pintype "passive"))
      (node (ref "C38") (pin "2") (pinfunction "2_2") (pintype "passive"))
      (node (ref "C40") (pin "2") (pinfunction "2_2") (pintype "passive"))
      (node (ref "C41") (pin "1") (pinfunction "1_1") (pintype "passive"))
      (node (ref "C42") (pin "1") (pinfunction "1_1") (pintype "passive"))
      (node (ref "C44") (pin "1") (pinfunction "1_1") (pintype "passive"))
      (node (ref "C57") (pin "2") (pinfunction "2_2") (pintype "passive"))
      (node (ref "C58") (pin "2") (pinfunction "2_2") (pintype "passive"))
      (node (ref "C59") (pin "1") (pinfunction "1_1") (pintype "passive"))
      (node (ref "C61") (pin "2") (pinfunction "2_2") (pintype "passive"))
      (node (ref "C82") (pin "2") (pinfunction "2_2") (pintype "passive"))
      (node (ref "C83") (pin "2") (pinfunction "2_2") (pintype "passive"))
      (node (ref "C85") (pin "1") (pinfunction "1_1") (pintype "passive"))
      (node (ref "D2") (pin "1") (pinfunction "1_1") (pintype "passive"))
      (node (ref "D3") (pin "1") (pinfunction "1_1") (pintype "passive"))
      (node (ref "D5") (pin "1") (pinfunction "1_1") (pintype "passive"))
      (node (ref "D6") (pin "1") (pinfunction "1_1") (pintype "passive"))
      (node (ref "U11") (pin "4") (pintype "passive"))
      (node (ref "U28") (pin "4") (pintype "passive"))
      (node (ref "U29") (pin "4") (pintype "passive"))
      (node (ref "U30") (pin "4") (pintype "passive"))
      (node (ref "U4") (pin "4") (pinfunction "-VS_4") (pintype "power_in"))
      (node (ref "U5") (pin "4") (pinfunction "-VS_4") (pintype "power_in"))
      (node (ref "U6") (pin "3") (pinfunction "VSS_3") (pintype "passive"))
      (node (ref "U7") (pin "4") (pinfunction "-VS_4") (pintype "power_in"))
      (node (ref "U8") (pin "4") (pinfunction "-VS_4") (pintype "power_in"))
      (node (ref "U9") (pin "6") (pinfunction "V-_6") (pintype "power_in"))
    )
    (net (code "26") (name "A_5V_P") (class "Default")
      (node (ref "C20") (pin "1") (pinfunction "1_1") (pintype "passive"))
      (node (ref "C21") (pin "1") (pinfunction "1_1") (pintype "passive"))
      (node (ref "C22") (pin "1") (pinfunction "1_1") (pintype "passive"))
      (node (ref "C23") (pin "1") (pinfunction "1_1") (pintype "passive"))
      (node (ref "C30") (pin "1") (pinfunction "1_1") (pintype "passive"))
      (node (ref "C31") (pin "1") (pinfunction "1_1") (pintype "passive"))
      (node (ref "C33") (pin "1") (pinfunction "1_1") (pintype "passive"))
      (node (ref "C34") (pin "1") (pinfunction "1_1") (pintype "passive"))
      (node (ref "C35") (pin "1") (pinfunction "1_1") (pintype "passive"))
      (node (ref "C36") (pin "1") (pinfunction "1_1") (pintype "passive"))
      (node (ref "C37") (pin "1") (pinfunction "1_1") (pintype "passive"))
      (node (ref "C47") (pin "1") (pinfunction "1_1") (pintype "passive"))
      (node (ref "C49") (pin "1") (pinfunction "1_1") (pintype "passive"))
      (node (ref "C50") (pin "1") (pinfunction "1_1") (pintype "passive"))
      (node (ref "C52") (pin "1") (pinfunction "1_1") (pintype "passive"))
      (node (ref "C70") (pin "1") (pinfunction "1_1") (pintype "passive"))
      (node (ref "C71") (pin "1") (pinfunction "1_1") (pintype "passive"))
      (node (ref "C73") (pin "1") (pinfunction "1_1") (pintype "passive"))
      (node (ref "C78") (pin "1") (pinfunction "1_1") (pintype "passive"))
      (node (ref "C89") (pin "1") (pinfunction "1_1") (pintype "passive"))
      (node (ref "C90") (pin "1") (pinfunction "1_1") (pintype "passive"))
      (node (ref "C91") (pin "2") (pinfunction "2_2") (pintype "passive"))
      (node (ref "D2") (pin "2") (pinfunction "2_2") (pintype "passive"))
      (node (ref "D3") (pin "2") (pinfunction "2_2") (pintype "passive"))
      (node (ref "D5") (pin "2") (pinfunction "2_2") (pintype "passive"))
      (node (ref "D6") (pin "2") (pinfunction "2_2") (pintype "passive"))
      (node (ref "L4") (pin "2") (pinfunction "2_2") (pintype "passive"))
      (node (ref "R25") (pin "2") (pinfunction "2_2") (pintype "passive"))
      (node (ref "R68") (pin "1") (pinfunction "1_1") (pintype "passive"))
      (node (ref "R69") (pin "2") (pinfunction "2_2") (pintype "passive"))
      (node (ref "U10") (pin "15") (pinfunction "AVDD1_15") (pintype "passive"))
      (node (ref "U10") (pin "26") (pinfunction "AVDD2_26") (pintype "passive"))
      (node (ref "U11") (pin "8") (pintype "passive"))
      (node (ref "U12") (pin "2") (pinfunction "VIN_2") (pintype "passive"))
      (node (ref "U28") (pin "8") (pintype "passive"))
      (node (ref "U29") (pin "8") (pintype "passive"))
      (node (ref "U30") (pin "8") (pintype "passive"))
      (node (ref "U4") (pin "7") (pinfunction "+VS_7") (pintype "power_in"))
      (node (ref "U5") (pin "7") (pinfunction "+VS_7") (pintype "power_in"))
      (node (ref "U6") (pin "12") (pinfunction "VDD_12") (pintype "passive"))
      (node (ref "U7") (pin "7") (pinfunction "+VS_7") (pintype "power_in"))
      (node (ref "U8") (pin "7") (pinfunction "+VS_7") (pintype "power_in"))
      (node (ref "U9") (pin "3") (pinfunction "V+_3") (pintype "power_in"))
    )
    (net (code "27") (name "GND") (class "Default")
      (node (ref "C167") (pin "1") (pinfunction "1_1") (pintype "passive"))
      (node (ref "C20") (pin "2") (pinfunction "2_2") (pintype "passive"))
      (node (ref "C21") (pin "2") (pinfunction "2_2") (pintype "passive"))
      (node (ref "C22") (pin "2") (pinfunction "2_2") (pintype "passive"))
      (node (ref "C23") (pin "2") (pinfunction "2_2") (pintype "passive"))
      (node (ref "C25") (pin "1") (pinfunction "1_1") (pintype "passive"))
      (node (ref "C26") (pin "2") (pinfunction "2_2") (pintype "passive"))
      (node (ref "C27") (pin "1") (pinfunction "1_1") (pintype "passive"))
      (node (ref "C28") (pin "2") (pinfunction "2_2") (pintype "passive"))
      (node (ref "C29") (pin "2") (pinfunction "2_2") (pintype "passive"))
      (node (ref "C30") (pin "2") (pinfunction "2_2") (pintype "passive"))
      (node (ref "C31") (pin "2") (pinfunction "2_2") (pintype "passive"))
      (node (ref "C32") (pin "2") (pinfunction "2_2") (pintype "passive"))
      (node (ref "C33") (pin "2") (pinfunction "2_2") (pintype "passive"))
      (node (ref "C34") (pin "2") (pinfunction "2_2") (pintype "passive"))
      (node (ref "C35") (pin "2") (pinfunction "2_2") (pintype "passive"))
      (node (ref "C36") (pin "2") (pinfunction "2_2") (pintype "passive"))
      (node (ref "C37") (pin "2") (pinfunction "2_2") (pintype "passive"))
      (node (ref "C38") (pin "1") (pinfunction "1_1") (pintype "passive"))
      (node (ref "C39") (pin "2") (pinfunction "2_2") (pintype "passive"))
      (node (ref "C40") (pin "1") (pinfunction "1_1") (pintype "passive"))
      (node (ref "C41") (pin "2") (pinfunction "2_2") (pintype "passive"))
      (node (ref "C42") (pin "2") (pinfunction "2_2") (pintype "passive"))
      (node (ref "C44") (pin "2") (pinfunction "2_2") (pintype "passive"))
      (node (ref "C47") (pin "2") (pinfunction "2_2") (pintype "passive"))
      (node (ref "C48") (pin "2") (pinfunction "2_2") (pintype "passive"))
      (node (ref "C49") (pin "2") (pinfunction "2_2") (pintype "passive"))
      (node (ref "C50") (pin "2") (pinfunction "2_2") (pintype "passive"))
      (node (ref "C52") (pin "2") (pinfunction "2_2") (pintype "passive"))
      (node (ref "C57") (pin "1") (pinfunction "1_1") (pintype "passive"))
      (node (ref "C58") (pin "1") (pinfunction "1_1") (pintype "passive"))
      (node (ref "C59") (pin "2") (pinfunction "2_2") (pintype "passive"))
      (node (ref "C61") (pin "1") (pinfunction "1_1") (pintype "passive"))
      (node (ref "C62") (pin "1") (pinfunction "1_1") (pintype "passive"))
      (node (ref "C66") (pin "1") (pinfunction "1_1") (pintype "passive"))
      (node (ref "C67") (pin "2") (pinfunction "2_2") (pintype "passive"))
      (node (ref "C70") (pin "2") (pinfunction "2_2") (pintype "passive"))
      (node (ref "C71") (pin "2") (pinfunction "2_2") (pintype "passive"))
      (node (ref "C73") (pin "2") (pinfunction "2_2") (pintype "passive"))
      (node (ref "C74") (pin "2") (pinfunction "2_2") (pintype "passive"))
      (node (ref "C76") (pin "2") (pinfunction "2_2") (pintype "passive"))
      (node (ref "C77") (pin "2") (pinfunction "2_2") (pintype "passive"))
      (node (ref "C78") (pin "2") (pinfunction "2_2") (pintype "passive"))
      (node (ref "C82") (pin "1") (pinfunction "1_1") (pintype "passive"))
      (node (ref "C83") (pin "1") (pinfunction "1_1") (pintype "passive"))
      (node (ref "C85") (pin "2") (pinfunction "2_2") (pintype "passive"))
      (node (ref "C86") (pin "2") (pinfunction "2_2") (pintype "passive"))
      (node (ref "C87") (pin "2") (pinfunction "2_2") (pintype "passive"))
      (node (ref "C88") (pin "2") (pinfunction "2_2") (pintype "passive"))
      (node (ref "C89") (pin "2") (pinfunction "2_2") (pintype "passive"))
      (node (ref "C90") (pin "2") (pinfunction "2_2") (pintype "passive"))
      (node (ref "C91") (pin "1") (pinfunction "1_1") (pintype "passive"))
      (node (ref "R13") (pin "1") (pinfunction "1_1") (pintype "passive"))
      (node (ref "R146") (pin "1") (pinfunction "1_1") (pintype "passive"))
      (node (ref "R15") (pin "2") (pinfunction "2_2") (pintype "passive"))
      (node (ref "R19") (pin "2") (pinfunction "2_2") (pintype "passive"))
      (node (ref "R20") (pin "1") (pinfunction "1_1") (pintype "passive"))
      (node (ref "R21") (pin "1") (pinfunction "1_1") (pintype "passive"))
      (node (ref "R22") (pin "1") (pinfunction "1_1") (pintype "passive"))
      (node (ref "R29") (pin "1") (pinfunction "1_1") (pintype "passive"))
      (node (ref "R34") (pin "1") (pinfunction "1_1") (pintype "passive"))
      (node (ref "R37") (pin "1") (pinfunction "1_1") (pintype "passive"))
      (node (ref "R38") (pin "1") (pinfunction "1_1") (pintype "passive"))
      (node (ref "R49") (pin "1") (pinfunction "1_1") (pintype "passive"))
      (node (ref "R52") (pin "1") (pinfunction "1_1") (pintype "passive"))
      (node (ref "R57") (pin "1") (pinfunction "1_1") (pintype "passive"))
      (node (ref "R73") (pin "1") (pinfunction "1_1") (pintype "passive"))
      (node (ref "R74") (pin "1") (pinfunction "1_1") (pintype "passive"))
      (node (ref "R76") (pin "1") (pinfunction "1_1") (pintype "passive"))
      (node (ref "R77") (pin "1") (pinfunction "1_1") (pintype "passive"))
      (node (ref "U10") (pin "16") (pinfunction "AGND1_16") (pintype "passive"))
      (node (ref "U10") (pin "19") (pinfunction "REFCOM_19") (pintype "passive"))
      (node (ref "U10") (pin "25") (pinfunction "AGND2_25") (pintype "passive"))
      (node (ref "U10") (pin "27") (pinfunction "DGND_27") (pintype "passive"))
      (node (ref "U12") (pin "4") (pinfunction "GND_4") (pintype "passive"))
      (node (ref "U28") (pin "5") (pinfunction "+_5") (pintype "passive"))
      (node (ref "U29") (pin "3") (pinfunction "+_3") (pintype "passive"))
      (node (ref "U29") (pin "5") (pinfunction "+_5") (pintype "passive"))
      (node (ref "U30") (pin "3") (pinfunction "+_3") (pintype "passive"))
      (node (ref "U6") (pin "13") (pinfunction "GND_13") (pintype "passive"))
    )
    (net (code "28") (name "Net-(C43-Pad1)") (class "Default")
      (node (ref "C43") (pin "1") (pinfunction "1_1") (pintype "passive"))
      (node (ref "C54") (pin "1") (pinfunction "1_1") (pintype "passive"))
      (node (ref "R45") (pin "2") (pinfunction "2_2") (pintype "passive"))
      (node (ref "R49") (pin "2") (pinfunction "2_2") (pintype "passive"))
    )
    (net (code "29") (name "Net-(C45-Pad2)") (class "Default")
      (node (ref "C45") (pin "2") (pinfunction "2_2") (pintype "passive"))
      (node (ref "C55") (pin "2") (pinfunction "2_2") (pintype "passive"))
      (node (ref "R47") (pin "2") (pinfunction "2_2") (pintype "passive"))
    )
    (net (code "30") (name "Net-(C46-Pad1)") (class "Default")
      (node (ref "C46") (pin "1") (pinfunction "1_1") (pintype "passive"))
      (node (ref "C56") (pin "1") (pinfunction "1_1") (pintype "passive"))
      (node (ref "R48") (pin "2") (pinfunction "2_2") (pintype "passive"))
      (node (ref "R52") (pin "2") (pinfunction "2_2") (pintype "passive"))
    )
    (net (code "31") (name "Net-(C68-Pad1)") (class "Default")
      (node (ref "C68") (pin "1") (pinfunction "1_1") (pintype "passive"))
      (node (ref "C79") (pin "1") (pinfunction "1_1") (pintype "passive"))
      (node (ref "R70") (pin "2") (pinfunction "2_2") (pintype "passive"))
      (node (ref "R73") (pin "2") (pinfunction "2_2") (pintype "passive"))
    )
    (net (code "32") (name "Net-(C69-Pad1)") (class "Default")
      (node (ref "C69") (pin "1") (pinfunction "1_1") (pintype "passive"))
      (node (ref "C80") (pin "1") (pinfunction "1_1") (pintype "passive"))
      (node (ref "R71") (pin "2") (pinfunction "2_2") (pintype "passive"))
      (node (ref "R74") (pin "2") (pinfunction "2_2") (pintype "passive"))
    )
    (net (code "33") (name "Net-(R35-Pad2)") (class "Default")
      (node (ref "R35") (pin "2") (pinfunction "2_2") (pintype "passive"))
      (node (ref "R36") (pin "1") (pinfunction "1_1") (pintype "passive"))
    )
    (net (code "34") (name "Net-(R39-Pad2)") (class "Default")
      (node (ref "R39") (pin "2") (pinfunction "2_2") (pintype "passive"))
      (node (ref "R40") (pin "1") (pinfunction "1_1") (pintype "passive"))
    )
    (net (code "35") (name "Net-(R145-Pad2)") (class "Default")
      (node (ref "R145") (pin "2") (pinfunction "2_2") (pintype "passive"))
      (node (ref "R146") (pin "2") (pinfunction "2_2") (pintype "passive"))
      (node (ref "R75") (pin "1") (pinfunction "1_1") (pintype "passive"))
    )
    (net (code "36") (name "Net-(U4-+IN)") (class "Default")
      (node (ref "R16") (pin "2") (pinfunction "2_2") (pintype "passive"))
      (node (ref "R20") (pin "2") (pinfunction "2_2") (pintype "passive"))
      (node (ref "U4") (pin "3") (pinfunction "+IN_3") (pintype "input"))
    )
    (net (code "37") (name "Net-(U4--IN)") (class "Default")
      (node (ref "R11") (pin "1") (pinfunction "1_1") (pintype "passive"))
      (node (ref "R13") (pin "2") (pinfunction "2_2") (pintype "passive"))
      (node (ref "U4") (pin "2") (pinfunction "-IN_2") (pintype "input"))
    )
    (net (code "38") (name "Net-(U4-OUT)") (class "Default")
      (node (ref "R11") (pin "2") (pinfunction "2_2") (pintype "passive"))
      (node (ref "R14") (pin "1") (pinfunction "1_1") (pintype "passive"))
      (node (ref "U4") (pin "6") (pinfunction "OUT_6") (pintype "output"))
    )
    (net (code "39") (name "Net-(U5-+IN)") (class "Default")
      (node (ref "R18") (pin "2") (pinfunction "2_2") (pintype "passive"))
      (node (ref "R22") (pin "2") (pinfunction "2_2") (pintype "passive"))
      (node (ref "U5") (pin "3") (pinfunction "+IN_3") (pintype "input"))
    )
    (net (code "40") (name "Net-(U5--IN)") (class "Default")
      (node (ref "R12") (pin "1") (pinfunction "1_1") (pintype "passive"))
      (node (ref "R14") (pin "2") (pinfunction "2_2") (pintype "passive"))
      (node (ref "U5") (pin "2") (pinfunction "-IN_2") (pintype "input"))
    )
    (net (code "41") (name "Net-(U5-OUT)") (class "Default")
      (node (ref "R12") (pin "2") (pinfunction "2_2") (pintype "passive"))
      (node (ref "R17") (pin "1") (pinfunction "1_1") (pintype "passive"))
      (node (ref "U5") (pin "6") (pinfunction "OUT_6") (pintype "output"))
    )
    (net (code "42") (name "Net-(U6-D)") (class "Default")
      (node (ref "C24") (pin "1") (pinfunction "1_1") (pintype "passive"))
      (node (ref "U6") (pin "6") (pinfunction "D_6") (pintype "passive"))
    )
    (net (code "43") (name "Net-(U6-EN)") (class "Default")
      (node (ref "R25") (pin "1") (pinfunction "1_1") (pintype "passive"))
      (node (ref "U6") (pin "2") (pinfunction "EN_2") (pintype "passive"))
    )
    (net (code "44") (name "Net-(U6-S1)") (class "Default")
      (node (ref "R15") (pin "1") (pinfunction "1_1") (pintype "passive"))
      (node (ref "U6") (pin "4") (pinfunction "S1_4") (pintype "passive"))
    )
    (net (code "45") (name "Net-(U6-S2)") (class "Default")
      (node (ref "C26") (pin "1") (pinfunction "1_1") (pintype "passive"))
      (node (ref "R17") (pin "2") (pinfunction "2_2") (pintype "passive"))
      (node (ref "U6") (pin "5") (pinfunction "S2_5") (pintype "passive"))
    )
    (net (code "46") (name "Net-(U6-S3)") (class "Default")
      (node (ref "C39") (pin "1") (pinfunction "1_1") (pintype "passive"))
      (node (ref "R31") (pin "2") (pinfunction "2_2") (pintype "passive"))
      (node (ref "U6") (pin "11") (pinfunction "S3_11") (pintype "passive"))
    )
    (net (code "47") (name "Net-(U6-S4)") (class "Default")
      (node (ref "R19") (pin "1") (pinfunction "1_1") (pintype "passive"))
      (node (ref "U6") (pin "10") (pinfunction "S4_10") (pintype "passive"))
    )
    (net (code "48") (name "Net-(U7-+IN)") (class "Default")
      (node (ref "R32") (pin "2") (pinfunction "2_2") (pintype "passive"))
      (node (ref "R37") (pin "2") (pinfunction "2_2") (pintype "passive"))
      (node (ref "U7") (pin "3") (pinfunction "+IN_3") (pintype "input"))
    )
    (net (code "49") (name "Net-(U7--IN)") (class "Default")
      (node (ref "R27") (pin "1") (pinfunction "1_1") (pintype "passive"))
      (node (ref "R29") (pin "2") (pinfunction "2_2") (pintype "passive"))
      (node (ref "U7") (pin "2") (pinfunction "-IN_2") (pintype "input"))
    )
    (net (code "50") (name "Net-(U7-OUT)") (class "Default")
      (node (ref "R27") (pin "2") (pinfunction "2_2") (pintype "passive"))
      (node (ref "R30") (pin "1") (pinfunction "1_1") (pintype "passive"))
      (node (ref "U7") (pin "6") (pinfunction "OUT_6") (pintype "output"))
    )
    (net (code "51") (name "Net-(U8-+IN)") (class "Default")
      (node (ref "R33") (pin "2") (pinfunction "2_2") (pintype "passive"))
      (node (ref "R38") (pin "2") (pinfunction "2_2") (pintype "passive"))
      (node (ref "U8") (pin "3") (pinfunction "+IN_3") (pintype "input"))
    )
    (net (code "52") (name "Net-(U8--IN)") (class "Default")
      (node (ref "R26") (pin "1") (pinfunction "1_1") (pintype "passive"))
      (node (ref "R30") (pin "2") (pinfunction "2_2") (pintype "passive"))
      (node (ref "U8") (pin "2") (pinfunction "-IN_2") (pintype "input"))
    )
    (net (code "53") (name "Net-(U8-OUT)") (class "Default")
      (node (ref "R26") (pin "2") (pinfunction "2_2") (pintype "passive"))
      (node (ref "R31") (pin "1") (pinfunction "1_1") (pintype "passive"))
      (node (ref "U8") (pin "6") (pinfunction "OUT_6") (pintype "output"))
    )
    (net (code "54") (name "Net-(U9-Din+)") (class "Default")
      (node (ref "R41") (pin "2") (pinfunction "2_2") (pintype "passive"))
      (node (ref "R46") (pin "1") (pinfunction "1_1") (pintype "passive"))
      (node (ref "U9") (pin "8") (pinfunction "Din+_8") (pintype "input"))
    )
    (net (code "55") (name "Net-(U9-Din-)") (class "Default")
      (node (ref "R28") (pin "1") (pinfunction "1_1") (pintype "passive"))
      (node (ref "R34") (pin "2") (pinfunction "2_2") (pintype "passive"))
      (node (ref "U9") (pin "1") (pinfunction "Din-_1") (pintype "input"))
    )
    (net (code "56") (name "Net-(U9-OUT+)") (class "Default")
      (node (ref "R28") (pin "2") (pinfunction "2_2") (pintype "passive"))
      (node (ref "R35") (pin "1") (pinfunction "1_1") (pintype "passive"))
      (node (ref "U9") (pin "4") (pinfunction "OUT+_4") (pintype "passive"))
    )
    (net (code "57") (name "Net-(U9-OUT-)") (class "Default")
      (node (ref "R39") (pin "1") (pinfunction "1_1") (pintype "passive"))
      (node (ref "R46") (pin "2") (pinfunction "2_2") (pintype "passive"))
      (node (ref "U9") (pin "5") (pinfunction "OUT-_5") (pintype "passive"))
    )
    (net (code "58") (name "Net-(U10-CAPB)") (class "Default")
      (node (ref "C64") (pin "2") (pinfunction "2_2") (pintype "passive"))
      (node (ref "C65") (pin "2") (pinfunction "2_2") (pintype "passive"))
      (node (ref "C66") (pin "2") (pinfunction "2_2") (pintype "passive"))
      (node (ref "U10") (pin "20") (pinfunction "CAPB_20") (pintype "passive"))
    )
    (net (code "59") (name "Net-(U10-CAPT)") (class "Default")
      (node (ref "C62") (pin "2") (pinfunction "2_2") (pintype "passive"))
      (node (ref "C64") (pin "1") (pinfunction "1_1") (pintype "passive"))
      (node (ref "C65") (pin "1") (pinfunction "1_1") (pintype "passive"))
      (node (ref "U10") (pin "21") (pinfunction "CAPT_21") (pintype "passive"))
    )
    (net (code "60") (name "Net-(U10-CLK)") (class "Default")
      (node (ref "R65") (pin "1") (pinfunction "1_1") (pintype "passive"))
      (node (ref "U10") (pin "1") (pinfunction "CLK_1") (pintype "passive"))
    )
    (net (code "61") (name "Net-(U10-CML)") (class "Default")
      (node (ref "C67") (pin "1") (pinfunction "1_1") (pintype "passive"))
      (node (ref "U10") (pin "22") (pinfunction "CML_22") (pintype "passive"))
    )
    (net (code "62") (name "Net-(U10-D0)") (class "Default")
      (node (ref "R51") (pin "1") (pinfunction "1_1") (pintype "passive"))
      (node (ref "U10") (pin "2") (pinfunction "D0_2") (pintype "passive"))
    )
    (net (code "63") (name "Net-(U10-D1)") (class "Default")
      (node (ref "R53") (pin "1") (pinfunction "1_1") (pintype "passive"))
      (node (ref "U10") (pin "3") (pinfunction "D1_3") (pintype "passive"))
    )
    (net (code "64") (name "Net-(U10-D2)") (class "Default")
      (node (ref "R54") (pin "1") (pinfunction "1_1") (pintype "passive"))
      (node (ref "U10") (pin "4") (pinfunction "D2_4") (pintype "passive"))
    )
    (net (code "65") (name "Net-(U10-D3)") (class "Default")
      (node (ref "R55") (pin "1") (pinfunction "1_1") (pintype "passive"))
      (node (ref "U10") (pin "5") (pinfunction "D3_5") (pintype "passive"))
    )
    (net (code "66") (name "Net-(U10-D4)") (class "Default")
      (node (ref "R56") (pin "1") (pinfunction "1_1") (pintype "passive"))
      (node (ref "U10") (pin "6") (pinfunction "D4_6") (pintype "passive"))
    )
    (net (code "67") (name "Net-(U10-D5)") (class "Default")
      (node (ref "R58") (pin "1") (pinfunction "1_1") (pintype "passive"))
      (node (ref "U10") (pin "7") (pinfunction "D5_7") (pintype "passive"))
    )
    (net (code "68") (name "Net-(U10-D6)") (class "Default")
      (node (ref "R59") (pin "1") (pinfunction "1_1") (pintype "passive"))
      (node (ref "U10") (pin "8") (pinfunction "D6_8") (pintype "passive"))
    )
    (net (code "69") (name "Net-(U10-D7)") (class "Default")
      (node (ref "R60") (pin "1") (pinfunction "1_1") (pintype "passive"))
      (node (ref "U10") (pin "9") (pinfunction "D7_9") (pintype "passive"))
    )
    (net (code "70") (name "Net-(U10-D8)") (class "Default")
      (node (ref "R61") (pin "1") (pinfunction "1_1") (pintype "passive"))
      (node (ref "U10") (pin "10") (pinfunction "D8_10") (pintype "passive"))
    )
    (net (code "71") (name "Net-(U10-D9)") (class "Default")
      (node (ref "R62") (pin "1") (pinfunction "1_1") (pintype "passive"))
      (node (ref "U10") (pin "11") (pinfunction "D9_11") (pintype "passive"))
    )
    (net (code "72") (name "Net-(U10-D10)") (class "Default")
      (node (ref "R63") (pin "1") (pinfunction "1_1") (pintype "passive"))
      (node (ref "U10") (pin "12") (pinfunction "D10_12") (pintype "passive"))
    )
    (net (code "73") (name "Net-(U10-D11)") (class "Default")
      (node (ref "R64") (pin "1") (pinfunction "1_1") (pintype "passive"))
      (node (ref "U10") (pin "13") (pinfunction "D11_13") (pintype "passive"))
    )
    (net (code "74") (name "Net-(U10-DVDD)") (class "Default")
      (node (ref "C76") (pin "1") (pinfunction "1_1") (pintype "passive"))
      (node (ref "C77") (pin "1") (pinfunction "1_1") (pintype "passive"))
      (node (ref "L4") (pin "1") (pinfunction "1_1") (pintype "passive"))
      (node (ref "R69") (pin "1") (pinfunction "1_1") (pintype "passive"))
      (node (ref "U10") (pin "28") (pinfunction "DVDD_28") (pintype "passive"))
    )
    (net (code "75") (name "Net-(U10-VINA)") (class "Default")
      (node (ref "R36") (pin "2") (pinfunction "2_2") (pintype "passive"))
      (node (ref "U10") (pin "23") (pinfunction "VINA_23") (pintype "passive"))
    )
    (net (code "76") (name "Net-(U10-VINB)") (class "Default")
      (node (ref "R40") (pin "2") (pinfunction "2_2") (pintype "passive"))
      (node (ref "U10") (pin "24") (pinfunction "VINB_24") (pintype "passive"))
    )
    (net (code "77") (name "Net-(U11A-+)") (class "Default")
      (node (ref "R77") (pin "2") (pinfunction "2_2") (pintype "passive"))
      (node (ref "U11") (pin "3") (pinfunction "+_3") (pintype "passive"))
    )
    (net (code "78") (name "Net-(U11A--)") (class "Default")
      (node (ref "R79") (pin "2") (pinfunction "2_2") (pintype "passive"))
      (node (ref "U11") (pin "2") (pinfunction "-_2") (pintype "passive"))
    )
    (net (code "79") (name "Net-(U11A-OUTA)") (class "Default")
      (node (ref "R79") (pin "1") (pinfunction "1_1") (pintype "passive"))
      (node (ref "U11") (pin "1") (pinfunction "OUTA_1") (pintype "passive"))
      (node (ref "out1") (pin "1") (pinfunction "TP_1") (pintype "passive"))
    )
    (net (code "80") (name "Net-(U11B-+)") (class "Default")
      (node (ref "R75") (pin "2") (pinfunction "2_2") (pintype "passive"))
      (node (ref "U11") (pin "5") (pinfunction "+_5") (pintype "passive"))
    )
    (net (code "81") (name "Net-(U11B--)") (class "Default")
      (node (ref "R78") (pin "1") (pinfunction "1_1") (pintype "passive"))
      (node (ref "U11") (pin "6") (pinfunction "-_6") (pintype "passive"))
    )
    (net (code "82") (name "Net-(U11B-OUTB)") (class "Default")
      (node (ref "C86") (pin "1") (pinfunction "1_1") (pintype "passive"))
      (node (ref "C88") (pin "1") (pinfunction "1_1") (pintype "passive"))
      (node (ref "R78") (pin "2") (pinfunction "2_2") (pintype "passive"))
      (node (ref "R80") (pin "1") (pinfunction "1_1") (pintype "passive"))
      (node (ref "U11") (pin "7") (pinfunction "OUTB_7") (pintype "passive"))
      (node (ref "VREF1") (pin "1") (pinfunction "TP_1") (pintype "passive"))
    )
    (net (code "83") (name "Net-(U12-Vount)") (class "Default")
      (node (ref "C167") (pin "2") (pinfunction "2_2") (pintype "passive"))
      (node (ref "R145") (pin "1") (pinfunction "1_1") (pintype "passive"))
      (node (ref "U12") (pin "6") (pinfunction "Vount_6") (pintype "passive"))
    )
    (net (code "84") (name "Net-(U28A-+)") (class "Default")
      (node (ref "R50") (pin "1") (pinfunction "1_1") (pintype "passive"))
      (node (ref "R57") (pin "2") (pinfunction "2_2") (pintype "passive"))
      (node (ref "U28") (pin "3") (pinfunction "+_3") (pintype "passive"))
    )
    (net (code "85") (name "Net-(U28A--)") (class "Default")
      (node (ref "C55") (pin "1") (pinfunction "1_1") (pintype "passive"))
      (node (ref "R43") (pin "1") (pinfunction "1_1") (pintype "passive"))
      (node (ref "U28") (pin "2") (pinfunction "-_2") (pintype "passive"))
    )
    (net (code "86") (name "Net-(U28A-OUTA)") (class "Default")
      (node (ref "C45") (pin "1") (pinfunction "1_1") (pintype "passive"))
      (node (ref "R43") (pin "2") (pinfunction "2_2") (pintype "passive"))
      (node (ref "R48") (pin "1") (pinfunction "1_1") (pintype "passive"))
      (node (ref "R50") (pin "2") (pinfunction "2_2") (pintype "passive"))
      (node (ref "U28") (pin "1") (pinfunction "OUTA_1") (pintype "passive"))
    )
    (net (code "87") (name "Net-(U28B--)") (class "Default")
      (node (ref "C56") (pin "2") (pinfunction "2_2") (pintype "passive"))
      (node (ref "R44") (pin "1") (pinfunction "1_1") (pintype "passive"))
      (node (ref "U28") (pin "6") (pinfunction "-_6") (pintype "passive"))
    )
    (net (code "88") (name "Net-(U28B-OUTB)") (class "Default")
      (node (ref "C46") (pin "2") (pinfunction "2_2") (pintype "passive"))
      (node (ref "R44") (pin "2") (pinfunction "2_2") (pintype "passive"))
      (node (ref "R45") (pin "1") (pinfunction "1_1") (pintype "passive"))
      (node (ref "U28") (pin "7") (pinfunction "OUTB_7") (pintype "passive"))
    )
    (net (code "89") (name "Net-(U29A--)") (class "Default")
      (node (ref "C54") (pin "2") (pinfunction "2_2") (pintype "passive"))
      (node (ref "R42") (pin "1") (pinfunction "1_1") (pintype "passive"))
      (node (ref "U29") (pin "2") (pinfunction "-_2") (pintype "passive"))
    )
    (net (code "90") (name "Net-(U29A-OUTA)") (class "Default")
      (node (ref "C43") (pin "2") (pinfunction "2_2") (pintype "passive"))
      (node (ref "R42") (pin "2") (pinfunction "2_2") (pintype "passive"))
      (node (ref "R70") (pin "1") (pinfunction "1_1") (pintype "passive"))
      (node (ref "U29") (pin "1") (pinfunction "OUTA_1") (pintype "passive"))
    )
    (net (code "91") (name "Net-(U29B--)") (class "Default")
      (node (ref "C79") (pin "2") (pinfunction "2_2") (pintype "passive"))
      (node (ref "R66") (pin "1") (pinfunction "1_1") (pintype "passive"))
      (node (ref "U29") (pin "6") (pinfunction "-_6") (pintype "passive"))
    )
    (net (code "92") (name "Net-(U29B-OUTB)") (class "Default")
      (node (ref "C68") (pin "2") (pinfunction "2_2") (pintype "passive"))
      (node (ref "R66") (pin "2") (pinfunction "2_2") (pintype "passive"))
      (node (ref "R71") (pin "1") (pinfunction "1_1") (pintype "passive"))
      (node (ref "U29") (pin "7") (pinfunction "OUTB_7") (pintype "passive"))
    )
    (net (code "93") (name "Net-(U30A--)") (class "Default")
      (node (ref "C80") (pin "2") (pinfunction "2_2") (pintype "passive"))
      (node (ref "R67") (pin "1") (pinfunction "1_1") (pintype "passive"))
      (node (ref "U30") (pin "2") (pinfunction "-_2") (pintype "passive"))
    )
    (net (code "94") (name "VREF") (class "Default")
      (node (ref "C48") (pin "1") (pinfunction "1_1") (pintype "passive"))
      (node (ref "C74") (pin "1") (pinfunction "1_1") (pintype "passive"))
      (node (ref "C87") (pin "1") (pinfunction "1_1") (pintype "passive"))
      (node (ref "R80") (pin "2") (pinfunction "2_2") (pintype "passive"))
      (node (ref "U10") (pin "18") (pinfunction "VREF_18") (pintype "passive"))
      (node (ref "U9") (pin "2") (pinfunction "Vcom_2") (pintype "passive"))
    )
    (net (code "95") (name "unconnected-(U6-NC1-Pad7)") (class "Default")
      (node (ref "U6") (pin "7") (pinfunction "NC1_7") (pintype "passive+no_connect"))
    )
    (net (code "96") (name "unconnected-(U6-NC2-Pad8)") (class "Default")
      (node (ref "U6") (pin "8") (pinfunction "NC2_8") (pintype "passive+no_connect"))
    )
    (net (code "97") (name "unconnected-(U6-NC3-Pad9)") (class "Default")
      (node (ref "U6") (pin "9") (pinfunction "NC3_9") (pintype "passive+no_connect"))
    )
    (net (code "98") (name "unconnected-(U9-NC-Pad7)") (class "Default")
      (node (ref "U9") (pin "7") (pinfunction "NC_7") (pintype "passive+no_connect"))
    )
    (net (code "99") (name "unconnected-(U10-ORT-Pad14)") (class "Default")
      (node (ref "U10") (pin "14") (pinfunction "ORT_14") (pintype "passive+no_connect"))
    )
    (net (code "100") (name "unconnected-(U12-DNC-Pad1)") (class "Default")
      (node (ref "U12") (pin "1") (pinfunction "DNC_1") (pintype "passive+no_connect"))
    )
    (net (code "101") (name "unconnected-(U12-DNC-Pad8)") (class "Default")
      (node (ref "U12") (pin "8") (pinfunction "DNC_8") (pintype "passive+no_connect"))
    )
    (net (code "102") (name "unconnected-(U12-NC-Pad7)") (class "Default")
      (node (ref "U12") (pin "7") (pinfunction "NC_7") (pintype "passive+no_connect"))
    )
    (net (code "103") (name "unconnected-(U12-TEMP-Pad3)") (class "Default")
      (node (ref "U12") (pin "3") (pinfunction "TEMP_3") (pintype "passive+no_connect"))
    )
    (net (code "104") (name "unconnected-(U12-TRIM-Pad5)") (class "Default")
      (node (ref "U12") (pin "5") (pinfunction "TRIM_5") (pintype "passive+no_connect"))
    )
  )
)
